# Power_Supply.net
KiCad netlist of a schematic drawn in Altium Designer
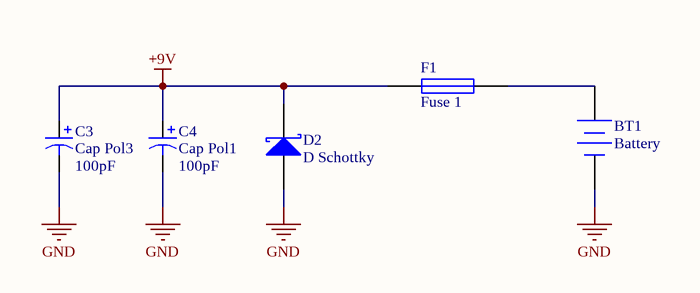
[diagram p0: Power Supply.SchDoc]

(export (version "E")
  (design (tool "Eeschema 10.0.6"))
  (components
    (comp (ref "BT1")
      (value "Battery")
      (footprint "BAT-2")
      (description "Multicell Battery")
      (fields (field (name "PUBLISHER") "Altium Limited"))
      (libsource (lib "Miscellaneous Devices") (part "Battery"))
    )
    (comp (ref "C3")
      (value "Cap Pol3")
      (footprint "C0805")
      (description "Polarized Capacitor (Surface Mount)")
      (fields (field (name "ALTIUM_VALUE") "100pF") (field (name "PUBLISHER") "Altium Limited"))
      (libsource (lib "Miscellaneous Devices") (part "Cap Pol3"))
    )
    (comp (ref "C4")
      (value "Cap Pol1")
      (footprint "RB7.6-15")
      (description "Polarized Capacitor (Radial)")
      (fields (field (name "ALTIUM_VALUE") "100pF") (field (name "PUBLISHER") "Altium Limited"))
      (libsource (lib "Miscellaneous Devices") (part "Cap Pol1"))
    )
    (comp (ref "D2")
      (value "D Schottky")
      (footprint "SMB")
      (description "Schottky Diode")
      (fields (field (name "PUBLISHER") "Altium Limited"))
      (libsource (lib "Miscellaneous Devices") (part "D Schottky"))
    )
    (comp (ref "F1")
      (value "Fuse 1")
      (footprint "PIN-W2/E2.8")
      (description "Fuse")
      (fields (field (name "PUBLISHER") "Altium Limited"))
      (libsource (lib "Miscellaneous Devices") (part "Fuse 1"))
    )
  )
  (nets
    (net (code "1") (name "+9V") (class "Default")
      (node (ref "C3") (pin "1") (pinfunction "1_1") (pintype "passive"))
      (node (ref "C4") (pin "1") (pinfunction "1_1") (pintype "passive"))
      (node (ref "D2") (pin "2") (pinfunction "K_2") (pintype "passive"))
      (node (ref "F1") (pin "1") (pinfunction "1_1") (pintype "passive"))
    )
    (net (code "2") (name "GND") (class "Default")
      (node (ref "BT1") (pin "2") (pinfunction "-_2") (pintype "passive"))
      (node (ref "C3") (pin "2") (pinfunction "2_2") (pintype "passive"))
      (node (ref "C4") (pin "2") (pinfunction "2_2") (pintype "passive"))
      (node (ref "D2") (pin "1") (pinfunction "A_1") (pintype "passive"))
    )
    (net (code "3") (name "Net-(BT1-+)") (class "Default")
      (node (ref "BT1") (pin "1") (pinfunction "+_1") (pintype "passive"))
      (node (ref "F1") (pin "2") (pinfunction "2_2") (pintype "passive"))
    )
  )
)
